# I3G.net
KiCad netlist of a schematic drawn in Altium Designer
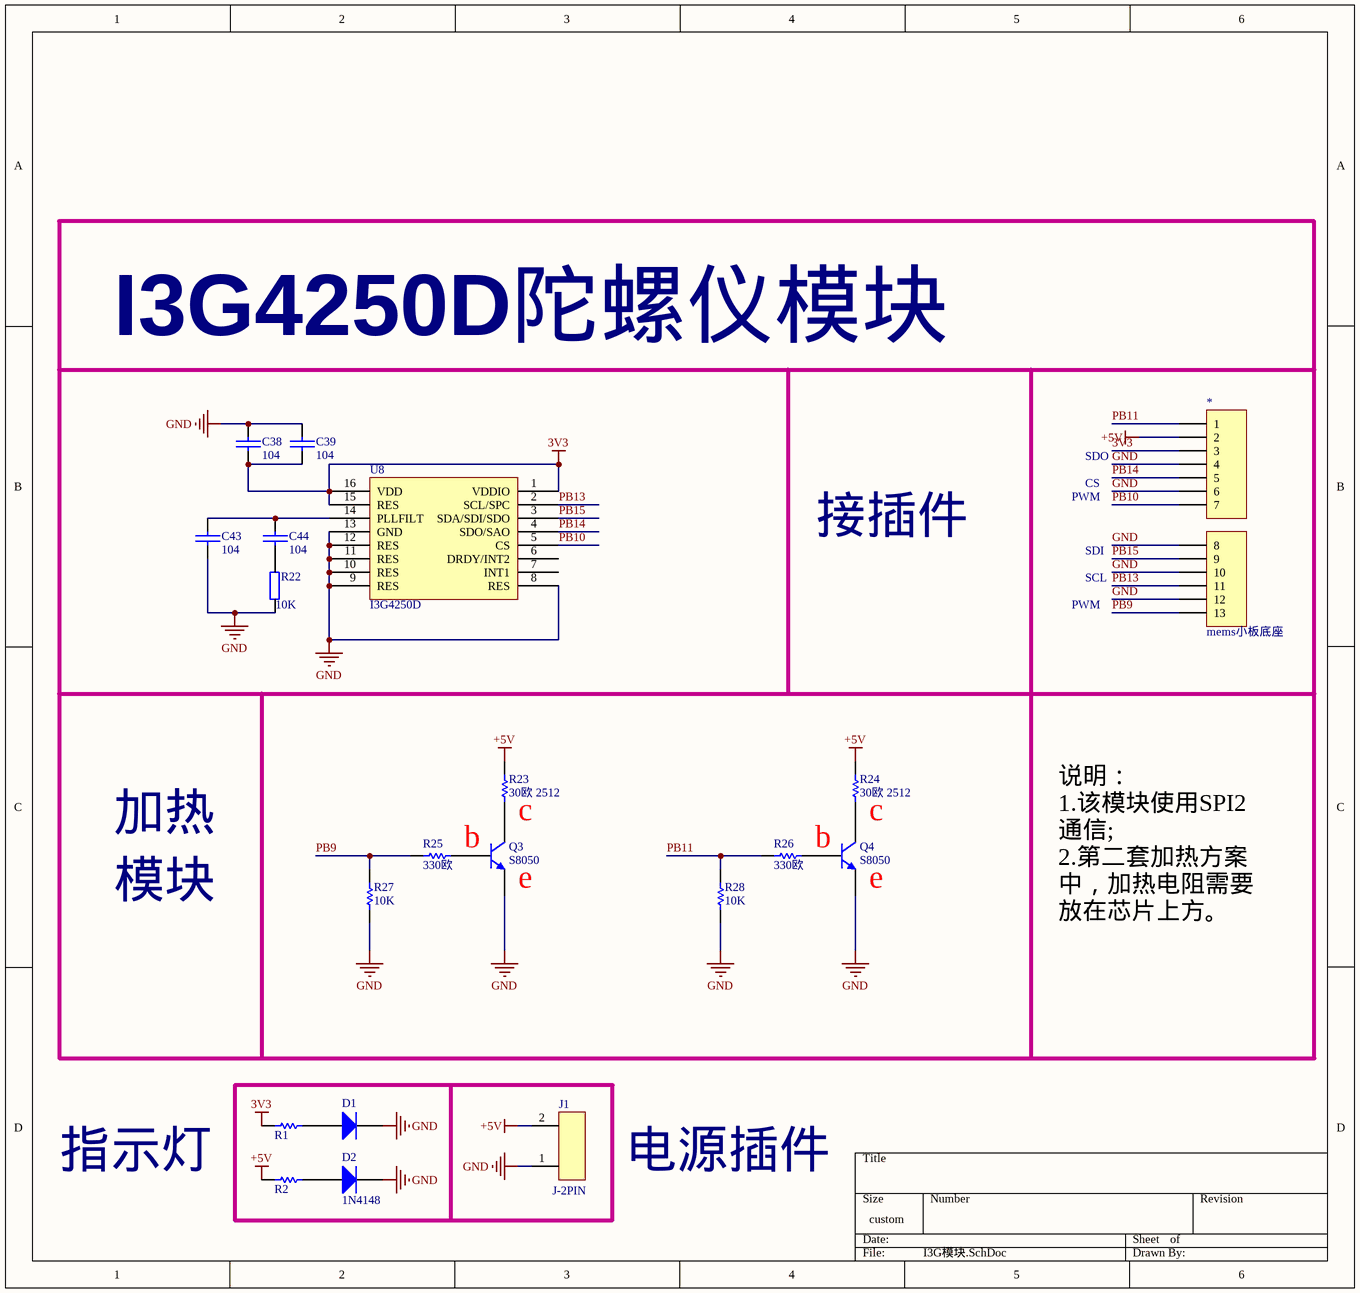
[diagram p0: I3G模块.SchDoc]

(export (version "E")
  (design (tool "Eeschema 10.0.6"))
  (components
    (comp (ref "*")
      (value "mems小板底座")
      (footprint "mems小板底座")
      (libsource (lib "ACTION原理图库") (part "mems小板底座"))
    )
    (comp (ref "C38")
      (value "104")
      (footprint "C-0805C")
      (description "Capacitor")
      (libsource (lib "ACTION原理图库") (part "C-贴片电容"))
    )
    (comp (ref "C39")
      (value "104")
      (footprint "C-0805C")
      (description "Capacitor")
      (libsource (lib "ACTION原理图库") (part "C-贴片电容"))
    )
    (comp (ref "C43")
      (value "104")
      (footprint "C-0805C")
      (description "Capacitor")
      (libsource (lib "ACTION原理图库") (part "C-贴片电容"))
    )
    (comp (ref "C44")
      (value "104")
      (footprint "C-0805C")
      (description "Capacitor")
      (libsource (lib "ACTION原理图库") (part "C-贴片电容"))
    )
    (comp (ref "D1")
      (value "~")
      (footprint "D-0603D")
      (description "Default Diode")
      (fields (field (name "PUBLISHER") "Altium Limited"))
      (libsource (lib "ACTION原理图库17.7.20修改版") (part "D-发光二极管"))
    )
    (comp (ref "D2")
      (value "1N4148")
      (footprint "D-0603D")
      (description "Default Diode")
      (fields (field (name "PUBLISHER") "Altium Limited"))
      (libsource (lib "ACTION原理图库17.7.20修改版") (part "D-发光二极管"))
    )
    (comp (ref "J1")
      (value "J-2PIN")
      (footprint "J-2-2.54-xh")
      (description "SOCKET")
      (libsource (lib "ACTION原理图库") (part "J-2PIN"))
    )
    (comp (ref "Q3")
      (value "S8050")
      (footprint "SOT-233-3")
      (description "NPN Bipolar Transistor")
      (fields (field (name "PUBLISHER") "Altium Limited"))
      (libsource (lib "Miscellaneous Devices") (part "NPN"))
    )
    (comp (ref "Q4")
      (value "S8050")
      (footprint "SOT-233-3")
      (description "NPN Bipolar Transistor")
      (fields (field (name "PUBLISHER") "Altium Limited"))
      (libsource (lib "Miscellaneous Devices") (part "NPN"))
    )
    (comp (ref "R1")
      (value "~")
      (footprint "R-0603R")
      (description "Resistor")
      (fields (field (name "PUBLISHER") "Altium Limited"))
      (libsource (lib "ACTION原理图库17.7.20修改版") (part "Resistor-1"))
    )
    (comp (ref "R2")
      (value "~")
      (footprint "R-0603R")
      (description "Resistor")
      (fields (field (name "PUBLISHER") "Altium Limited"))
      (libsource (lib "ACTION原理图库17.7.20修改版") (part "Resistor-1"))
    )
    (comp (ref "R22") (value "10K") (footprint "R-0603R") (libsource (lib "ACTION原理图库") (part "Resistor")))
    (comp (ref "R23")
      (value "30欧 2512")
      (footprint "R-3925R（锰铜）")
      (description "Semiconductor Resistor")
      (fields (field (name "PUBLISHER") "Altium Limited"))
      (libsource (lib "大赛无线手柄") (part "Res Semi"))
    )
    (comp (ref "R24")
      (value "30欧 2512")
      (footprint "PCBComponent_1")
      (description "Semiconductor Resistor")
      (fields (field (name "PUBLISHER") "Altium Limited"))
      (libsource (lib "大赛无线手柄") (part "Res Semi"))
    )
    (comp (ref "R25")
      (value "330欧")
      (footprint "R-0603R")
      (description "Semiconductor Resistor")
      (fields (field (name "PUBLISHER") "Altium Limited"))
      (libsource (lib "altium-import") (part "root_0_Res Semi_"))
    )
    (comp (ref "R26")
      (value "330欧")
      (footprint "R-0603R")
      (description "Semiconductor Resistor")
      (fields (field (name "PUBLISHER") "Altium Limited"))
      (libsource (lib "altium-import") (part "root_0_Res Semi_"))
    )
    (comp (ref "R27")
      (value "10K")
      (footprint "R-0603R")
      (description "Semiconductor Resistor")
      (fields (field (name "PUBLISHER") "Altium Limited"))
      (libsource (lib "大赛无线手柄") (part "Res Semi"))
    )
    (comp (ref "R28")
      (value "10K")
      (footprint "R-0603R")
      (description "Semiconductor Resistor")
      (fields (field (name "PUBLISHER") "Altium Limited"))
      (libsource (lib "大赛无线手柄") (part "Res Semi"))
    )
    (comp (ref "U8")
      (value "I3G4250D")
      (footprint "I3G4250D")
      (description "gyroscope")
      (libsource (lib "陀螺仪元件库") (part "I3G4250D"))
    )
  )
  (nets
    (net (code "1") (name "+5V") (class "Default")
      (node (ref "*") (pin "2") (pinfunction "2_2") (pintype "passive"))
      (node (ref "J1") (pin "2") (pinfunction "2_2") (pintype "passive"))
      (node (ref "R2") (pin "1") (pinfunction "1_1") (pintype "passive"))
      (node (ref "R23") (pin "2") (pinfunction "2_2") (pintype "passive"))
      (node (ref "R24") (pin "2") (pinfunction "2_2") (pintype "passive"))
    )
    (net (code "2") (name "/PB9") (class "Default")
      (node (ref "*") (pin "13") (pinfunction "13_13") (pintype "passive"))
      (node (ref "R25") (pin "1") (pinfunction "1_1") (pintype "passive"))
      (node (ref "R27") (pin "2") (pinfunction "2_2") (pintype "passive"))
    )
    (net (code "3") (name "/PB10") (class "Default")
      (node (ref "*") (pin "7") (pinfunction "7_7") (pintype "passive"))
      (node (ref "U8") (pin "5") (pinfunction "CS_5") (pintype "passive"))
    )
    (net (code "4") (name "/PB11") (class "Default")
      (node (ref "*") (pin "1") (pinfunction "1_1") (pintype "passive"))
      (node (ref "R26") (pin "1") (pinfunction "1_1") (pintype "passive"))
      (node (ref "R28") (pin "2") (pinfunction "2_2") (pintype "passive"))
    )
    (net (code "5") (name "/PB13") (class "Default")
      (node (ref "*") (pin "11") (pinfunction "11_11") (pintype "passive"))
      (node (ref "U8") (pin "2") (pinfunction "SCL/SPC_2") (pintype "passive"))
    )
    (net (code "6") (name "/PB14") (class "Default")
      (node (ref "*") (pin "5") (pinfunction "5_5") (pintype "passive"))
      (node (ref "U8") (pin "4") (pinfunction "SDO/SAO_4") (pintype "passive"))
    )
    (net (code "7") (name "/PB15") (class "Default")
      (node (ref "*") (pin "9") (pinfunction "9_9") (pintype "passive"))
      (node (ref "U8") (pin "3") (pinfunction "SDA/SDI/SDO_3") (pintype "passive"))
    )
    (net (code "8") (name "3V3") (class "Default")
      (node (ref "*") (pin "3") (pinfunction "3_3") (pintype "passive"))
      (node (ref "C38") (pin "2") (pinfunction "2_2") (pintype "passive"))
      (node (ref "C39") (pin "2") (pinfunction "2_2") (pintype "passive"))
      (node (ref "R1") (pin "1") (pinfunction "1_1") (pintype "passive"))
      (node (ref "U8") (pin "1") (pinfunction "VDDIO_1") (pintype "passive"))
      (node (ref "U8") (pin "15") (pinfunction "RES_15") (pintype "passive"))
      (node (ref "U8") (pin "16") (pinfunction "VDD_16") (pintype "passive"))
    )
    (net (code "9") (name "GND") (class "Default")
      (node (ref "*") (pin "10") (pinfunction "10_10") (pintype "passive"))
      (node (ref "*") (pin "12") (pinfunction "12_12") (pintype "passive"))
      (node (ref "*") (pin "4") (pinfunction "4_4") (pintype "passive"))
      (node (ref "*") (pin "6") (pinfunction "6_6") (pintype "passive"))
      (node (ref "*") (pin "8") (pinfunction "8_8") (pintype "passive"))
      (node (ref "C38") (pin "1") (pinfunction "1_1") (pintype "passive"))
      (node (ref "C39") (pin "1") (pinfunction "1_1") (pintype "passive"))
      (node (ref "C43") (pin "2") (pinfunction "2_2") (pintype "passive"))
      (node (ref "D1") (pin "2") (pinfunction "2_2") (pintype "passive"))
      (node (ref "D2") (pin "2") (pinfunction "2_2") (pintype "passive"))
      (node (ref "J1") (pin "1") (pinfunction "1_1") (pintype "passive"))
      (node (ref "Q3") (pin "3") (pinfunction "E_3") (pintype "passive"))
      (node (ref "Q4") (pin "3") (pinfunction "E_3") (pintype "passive"))
      (node (ref "R22") (pin "2") (pintype "passive"))
      (node (ref "R27") (pin "1") (pinfunction "1_1") (pintype "passive"))
      (node (ref "R28") (pin "1") (pinfunction "1_1") (pintype "passive"))
      (node (ref "U8") (pin "10") (pinfunction "RES_10") (pintype "passive"))
      (node (ref "U8") (pin "11") (pinfunction "RES_11") (pintype "passive"))
      (node (ref "U8") (pin "12") (pinfunction "RES_12") (pintype "passive"))
      (node (ref "U8") (pin "13") (pinfunction "GND_13") (pintype "passive"))
      (node (ref "U8") (pin "8") (pinfunction "RES_8") (pintype "passive"))
      (node (ref "U8") (pin "9") (pinfunction "RES_9") (pintype "passive"))
    )
    (net (code "10") (name "Net-(C44-Pad1)") (class "Default")
      (node (ref "C44") (pin "1") (pinfunction "1_1") (pintype "passive"))
      (node (ref "R22") (pin "1") (pintype "passive"))
    )
    (net (code "11") (name "Net-(D1-Pad1)") (class "Default")
      (node (ref "D1") (pin "1") (pinfunction "1_1") (pintype "passive"))
      (node (ref "R1") (pin "2") (pinfunction "2_2") (pintype "passive"))
    )
    (net (code "12") (name "Net-(D2-Pad1)") (class "Default")
      (node (ref "D2") (pin "1") (pinfunction "1_1") (pintype "passive"))
      (node (ref "R2") (pin "2") (pinfunction "2_2") (pintype "passive"))
    )
    (net (code "13") (name "Net-(Q3-B)") (class "Default")
      (node (ref "Q3") (pin "2") (pinfunction "B_2") (pintype "passive"))
      (node (ref "R25") (pin "2") (pinfunction "2_2") (pintype "passive"))
    )
    (net (code "14") (name "Net-(Q3-C)") (class "Default")
      (node (ref "Q3") (pin "1") (pinfunction "C_1") (pintype "passive"))
      (node (ref "R23") (pin "1") (pinfunction "1_1") (pintype "passive"))
    )
    (net (code "15") (name "Net-(Q4-B)") (class "Default")
      (node (ref "Q4") (pin "2") (pinfunction "B_2") (pintype "passive"))
      (node (ref "R26") (pin "2") (pinfunction "2_2") (pintype "passive"))
    )
    (net (code "16") (name "Net-(Q4-C)") (class "Default")
      (node (ref "Q4") (pin "1") (pinfunction "C_1") (pintype "passive"))
      (node (ref "R24") (pin "1") (pinfunction "1_1") (pintype "passive"))
    )
    (net (code "17") (name "Net-(U8-PLLFILT)") (class "Default")
      (node (ref "C43") (pin "1") (pinfunction "1_1") (pintype "passive"))
      (node (ref "C44") (pin "2") (pinfunction "2_2") (pintype "passive"))
      (node (ref "U8") (pin "14") (pinfunction "PLLFILT_14") (pintype "passive"))
    )
    (net (code "18") (name "unconnected-(U8-DRDY{slash}INT2-Pad6)") (class "Default")
      (node (ref "U8") (pin "6") (pinfunction "DRDY/INT2_6") (pintype "passive"))
    )
    (net (code "19") (name "unconnected-(U8-INT1-Pad7)") (class "Default")
      (node (ref "U8") (pin "7") (pinfunction "INT1_7") (pintype "passive"))
    )
  )
)
